# B167X.net
KiCad netlist of a schematic drawn in EAGLE
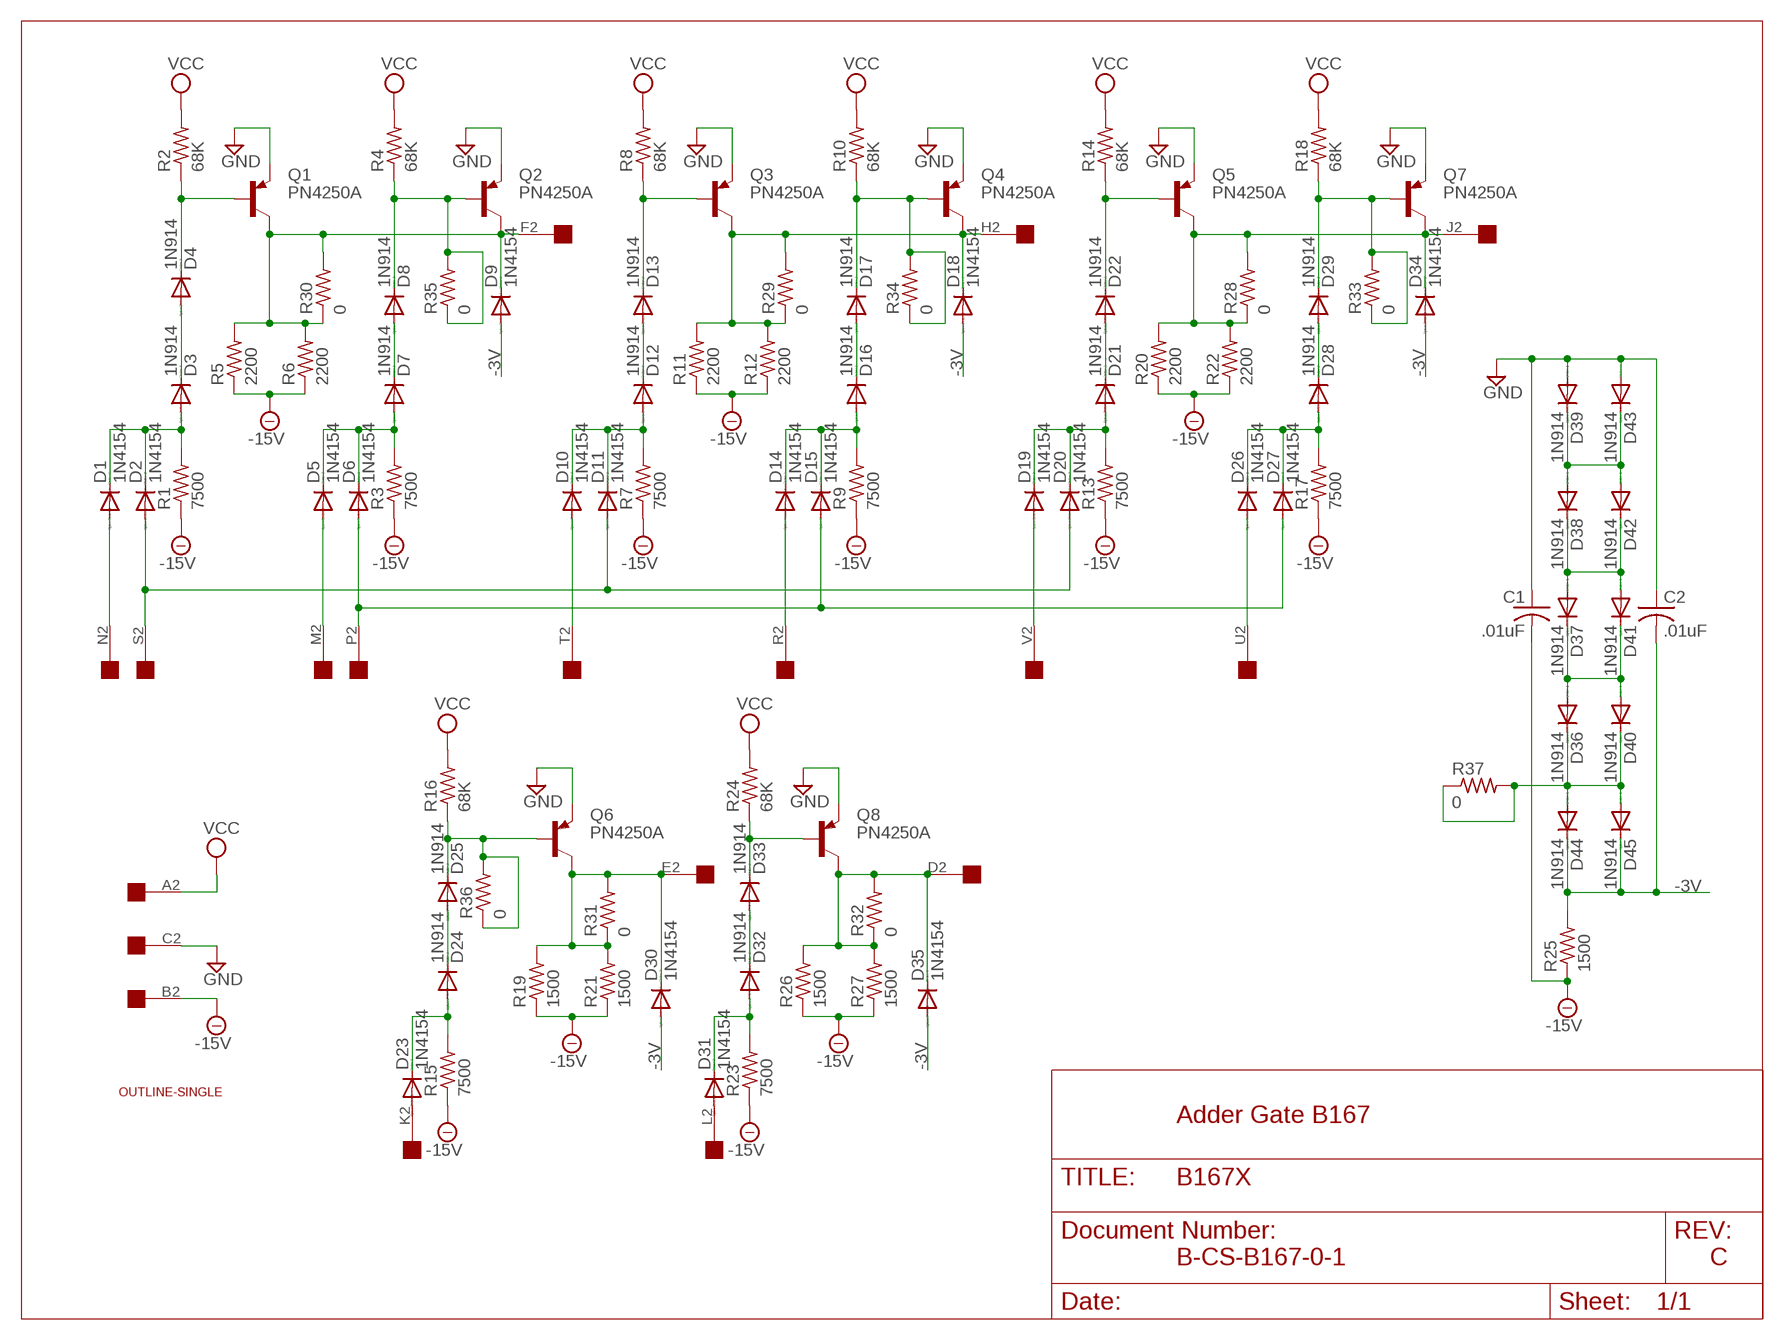
[diagram p0: schematic, sheet 1]

(export (version "E")
  (design (tool "Eeschema 10.0.6"))
  (components
    (comp (ref "C1")
      (value ".01uF")
      (footprint "eagle-import:C063-025X075")
      (libsource (lib "eagle-import") (part "C-US"))
    )
    (comp (ref "C2")
      (value ".01uF")
      (footprint "eagle-import:C063-025X075")
      (libsource (lib "eagle-import") (part "C-US"))
    )
    (comp (ref "D1")
      (value "1N4154")
      (footprint "eagle-import:DO35-10")
      (libsource (lib "eagle-import") (part "DIODE-DO35-10"))
    )
    (comp (ref "D2")
      (value "1N4154")
      (footprint "eagle-import:DO35-10")
      (libsource (lib "eagle-import") (part "DIODE-DO35-10"))
    )
    (comp (ref "D3")
      (value "1N914")
      (footprint "eagle-import:DO35-10")
      (libsource (lib "eagle-import") (part "DIODE-DO35-10"))
    )
    (comp (ref "D4")
      (value "1N914")
      (footprint "eagle-import:DO35-10")
      (libsource (lib "eagle-import") (part "DIODE-DO35-10"))
    )
    (comp (ref "D5")
      (value "1N4154")
      (footprint "eagle-import:DO35-10")
      (libsource (lib "eagle-import") (part "DIODE-DO35-10"))
    )
    (comp (ref "D6")
      (value "1N4154")
      (footprint "eagle-import:DO35-10")
      (libsource (lib "eagle-import") (part "DIODE-DO35-10"))
    )
    (comp (ref "D7")
      (value "1N914")
      (footprint "eagle-import:DO35-10")
      (libsource (lib "eagle-import") (part "DIODE-DO35-10"))
    )
    (comp (ref "D8")
      (value "1N914")
      (footprint "eagle-import:DO35-10")
      (libsource (lib "eagle-import") (part "DIODE-DO35-10"))
    )
    (comp (ref "D9")
      (value "1N4154")
      (footprint "eagle-import:DO35-10")
      (libsource (lib "eagle-import") (part "DIODE-DO35-10"))
    )
    (comp (ref "D10")
      (value "1N4154")
      (footprint "eagle-import:DO35-10")
      (libsource (lib "eagle-import") (part "DIODE-DO35-10"))
    )
    (comp (ref "D11")
      (value "1N4154")
      (footprint "eagle-import:DO35-10")
      (libsource (lib "eagle-import") (part "DIODE-DO35-10"))
    )
    (comp (ref "D12")
      (value "1N914")
      (footprint "eagle-import:DO35-10")
      (libsource (lib "eagle-import") (part "DIODE-DO35-10"))
    )
    (comp (ref "D13")
      (value "1N914")
      (footprint "eagle-import:DO35-10")
      (libsource (lib "eagle-import") (part "DIODE-DO35-10"))
    )
    (comp (ref "D14")
      (value "1N4154")
      (footprint "eagle-import:DO35-10")
      (libsource (lib "eagle-import") (part "DIODE-DO35-10"))
    )
    (comp (ref "D15")
      (value "1N4154")
      (footprint "eagle-import:DO35-10")
      (libsource (lib "eagle-import") (part "DIODE-DO35-10"))
    )
    (comp (ref "D16")
      (value "1N914")
      (footprint "eagle-import:DO35-10")
      (libsource (lib "eagle-import") (part "DIODE-DO35-10"))
    )
    (comp (ref "D17")
      (value "1N914")
      (footprint "eagle-import:DO35-10")
      (libsource (lib "eagle-import") (part "DIODE-DO35-10"))
    )
    (comp (ref "D18")
      (value "1N4154")
      (footprint "eagle-import:DO35-10")
      (libsource (lib "eagle-import") (part "DIODE-DO35-10"))
    )
    (comp (ref "D19")
      (value "1N4154")
      (footprint "eagle-import:DO35-10")
      (libsource (lib "eagle-import") (part "DIODE-DO35-10"))
    )
    (comp (ref "D20")
      (value "1N4154")
      (footprint "eagle-import:DO35-10")
      (libsource (lib "eagle-import") (part "DIODE-DO35-10"))
    )
    (comp (ref "D21")
      (value "1N914")
      (footprint "eagle-import:DO35-10")
      (libsource (lib "eagle-import") (part "DIODE-DO35-10"))
    )
    (comp (ref "D22")
      (value "1N914")
      (footprint "eagle-import:DO35-10")
      (libsource (lib "eagle-import") (part "DIODE-DO35-10"))
    )
    (comp (ref "D23")
      (value "1N4154")
      (footprint "eagle-import:DO35-10")
      (libsource (lib "eagle-import") (part "DIODE-DO35-10"))
    )
    (comp (ref "D24")
      (value "1N914")
      (footprint "eagle-import:DO35-10")
      (libsource (lib "eagle-import") (part "DIODE-DO35-10"))
    )
    (comp (ref "D25")
      (value "1N914")
      (footprint "eagle-import:DO35-10")
      (libsource (lib "eagle-import") (part "DIODE-DO35-10"))
    )
    (comp (ref "D26")
      (value "1N4154")
      (footprint "eagle-import:DO35-10")
      (libsource (lib "eagle-import") (part "DIODE-DO35-10"))
    )
    (comp (ref "D27")
      (value "1N4154")
      (footprint "eagle-import:DO35-10")
      (libsource (lib "eagle-import") (part "DIODE-DO35-10"))
    )
    (comp (ref "D28")
      (value "1N914")
      (footprint "eagle-import:DO35-10")
      (libsource (lib "eagle-import") (part "DIODE-DO35-10"))
    )
    (comp (ref "D29")
      (value "1N914")
      (footprint "eagle-import:DO35-10")
      (libsource (lib "eagle-import") (part "DIODE-DO35-10"))
    )
    (comp (ref "D30")
      (value "1N4154")
      (footprint "eagle-import:DO35-10")
      (libsource (lib "eagle-import") (part "DIODE-DO35-10"))
    )
    (comp (ref "D31")
      (value "1N4154")
      (footprint "eagle-import:DO35-10")
      (libsource (lib "eagle-import") (part "DIODE-DO35-10"))
    )
    (comp (ref "D32")
      (value "1N914")
      (footprint "eagle-import:DO35-10")
      (libsource (lib "eagle-import") (part "DIODE-DO35-10"))
    )
    (comp (ref "D33")
      (value "1N914")
      (footprint "eagle-import:DO35-10")
      (libsource (lib "eagle-import") (part "DIODE-DO35-10"))
    )
    (comp (ref "D34")
      (value "1N4154")
      (footprint "eagle-import:DO35-10")
      (libsource (lib "eagle-import") (part "DIODE-DO35-10"))
    )
    (comp (ref "D35")
      (value "1N4154")
      (footprint "eagle-import:DO35-10")
      (libsource (lib "eagle-import") (part "DIODE-DO35-10"))
    )
    (comp (ref "D36")
      (value "1N914")
      (footprint "eagle-import:DO35-10")
      (libsource (lib "eagle-import") (part "DIODE-DO35-10"))
    )
    (comp (ref "D37")
      (value "1N914")
      (footprint "eagle-import:DO35-10")
      (libsource (lib "eagle-import") (part "DIODE-DO35-10"))
    )
    (comp (ref "D38")
      (value "1N914")
      (footprint "eagle-import:DO35-10")
      (libsource (lib "eagle-import") (part "DIODE-DO35-10"))
    )
    (comp (ref "D39")
      (value "1N914")
      (footprint "eagle-import:DO35-10")
      (libsource (lib "eagle-import") (part "DIODE-DO35-10"))
    )
    (comp (ref "D40")
      (value "1N914")
      (footprint "eagle-import:DO35-10")
      (libsource (lib "eagle-import") (part "DIODE-DO35-10"))
    )
    (comp (ref "D41")
      (value "1N914")
      (footprint "eagle-import:DO35-10")
      (libsource (lib "eagle-import") (part "DIODE-DO35-10"))
    )
    (comp (ref "D42")
      (value "1N914")
      (footprint "eagle-import:DO35-10")
      (libsource (lib "eagle-import") (part "DIODE-DO35-10"))
    )
    (comp (ref "D43")
      (value "1N914")
      (footprint "eagle-import:DO35-10")
      (libsource (lib "eagle-import") (part "DIODE-DO35-10"))
    )
    (comp (ref "D44")
      (value "1N914")
      (footprint "eagle-import:DO35-10")
      (libsource (lib "eagle-import") (part "DIODE-DO35-10"))
    )
    (comp (ref "D45")
      (value "1N914")
      (footprint "eagle-import:DO35-10")
      (libsource (lib "eagle-import") (part "DIODE-DO35-10"))
    )
    (comp (ref "Q1")
      (value "PN4250A")
      (footprint "eagle-import:TO5")
      (libsource (lib "eagle-import") (part "-PNP-TO5"))
    )
    (comp (ref "Q2")
      (value "PN4250A")
      (footprint "eagle-import:TO5")
      (libsource (lib "eagle-import") (part "-PNP-TO5"))
    )
    (comp (ref "Q3")
      (value "PN4250A")
      (footprint "eagle-import:TO5")
      (libsource (lib "eagle-import") (part "-PNP-TO5"))
    )
    (comp (ref "Q4")
      (value "PN4250A")
      (footprint "eagle-import:TO5")
      (libsource (lib "eagle-import") (part "-PNP-TO5"))
    )
    (comp (ref "Q5")
      (value "PN4250A")
      (footprint "eagle-import:TO5")
      (libsource (lib "eagle-import") (part "-PNP-TO5"))
    )
    (comp (ref "Q6")
      (value "PN4250A")
      (footprint "eagle-import:TO5")
      (libsource (lib "eagle-import") (part "-PNP-TO5"))
    )
    (comp (ref "Q7")
      (value "PN4250A")
      (footprint "eagle-import:TO5")
      (libsource (lib "eagle-import") (part "-PNP-TO5"))
    )
    (comp (ref "Q8")
      (value "PN4250A")
      (footprint "eagle-import:TO5")
      (libsource (lib "eagle-import") (part "-PNP-TO5"))
    )
    (comp (ref "R1")
      (value "7500")
      (footprint "eagle-import:0207_10")
      (libsource (lib "eagle-import") (part "R-US_0207/10"))
    )
    (comp (ref "R2")
      (value "68K")
      (footprint "eagle-import:0207_10")
      (libsource (lib "eagle-import") (part "R-US_0207/10"))
    )
    (comp (ref "R3")
      (value "7500")
      (footprint "eagle-import:0207_10")
      (libsource (lib "eagle-import") (part "R-US_0207/10"))
    )
    (comp (ref "R4")
      (value "68K")
      (footprint "eagle-import:0207_10")
      (libsource (lib "eagle-import") (part "R-US_0207/10"))
    )
    (comp (ref "R5")
      (value "2200")
      (footprint "eagle-import:0207_10")
      (libsource (lib "eagle-import") (part "R-US_0207/10"))
    )
    (comp (ref "R6")
      (value "2200")
      (footprint "eagle-import:0207_10")
      (libsource (lib "eagle-import") (part "R-US_0207/10"))
    )
    (comp (ref "R7")
      (value "7500")
      (footprint "eagle-import:0207_10")
      (libsource (lib "eagle-import") (part "R-US_0207/10"))
    )
    (comp (ref "R8")
      (value "68K")
      (footprint "eagle-import:0207_10")
      (libsource (lib "eagle-import") (part "R-US_0207/10"))
    )
    (comp (ref "R9")
      (value "7500")
      (footprint "eagle-import:0207_10")
      (libsource (lib "eagle-import") (part "R-US_0207/10"))
    )
    (comp (ref "R10")
      (value "68K")
      (footprint "eagle-import:0207_10")
      (libsource (lib "eagle-import") (part "R-US_0207/10"))
    )
    (comp (ref "R11")
      (value "2200")
      (footprint "eagle-import:0207_10")
      (libsource (lib "eagle-import") (part "R-US_0207/10"))
    )
    (comp (ref "R12")
      (value "2200")
      (footprint "eagle-import:0207_10")
      (libsource (lib "eagle-import") (part "R-US_0207/10"))
    )
    (comp (ref "R13")
      (value "7500")
      (footprint "eagle-import:0207_10")
      (libsource (lib "eagle-import") (part "R-US_0207/10"))
    )
    (comp (ref "R14")
      (value "68K")
      (footprint "eagle-import:0207_10")
      (libsource (lib "eagle-import") (part "R-US_0207/10"))
    )
    (comp (ref "R15")
      (value "7500")
      (footprint "eagle-import:0207_10")
      (libsource (lib "eagle-import") (part "R-US_0207/10"))
    )
    (comp (ref "R16")
      (value "68K")
      (footprint "eagle-import:0207_10")
      (libsource (lib "eagle-import") (part "R-US_0207/10"))
    )
    (comp (ref "R17")
      (value "7500")
      (footprint "eagle-import:0207_10")
      (libsource (lib "eagle-import") (part "R-US_0207/10"))
    )
    (comp (ref "R18")
      (value "68K")
      (footprint "eagle-import:0207_10")
      (libsource (lib "eagle-import") (part "R-US_0207/10"))
    )
    (comp (ref "R19")
      (value "1500")
      (footprint "eagle-import:0207_10")
      (libsource (lib "eagle-import") (part "R-US_0207/10"))
    )
    (comp (ref "R20")
      (value "2200")
      (footprint "eagle-import:0207_10")
      (libsource (lib "eagle-import") (part "R-US_0207/10"))
    )
    (comp (ref "R21")
      (value "1500")
      (footprint "eagle-import:0207_10")
      (libsource (lib "eagle-import") (part "R-US_0207/10"))
    )
    (comp (ref "R22")
      (value "2200")
      (footprint "eagle-import:0207_10")
      (libsource (lib "eagle-import") (part "R-US_0207/10"))
    )
    (comp (ref "R23")
      (value "7500")
      (footprint "eagle-import:0207_10")
      (libsource (lib "eagle-import") (part "R-US_0207/10"))
    )
    (comp (ref "R24")
      (value "68K")
      (footprint "eagle-import:0207_10")
      (libsource (lib "eagle-import") (part "R-US_0207/10"))
    )
    (comp (ref "R25")
      (value "1500")
      (footprint "eagle-import:0207_10")
      (libsource (lib "eagle-import") (part "R-US_0207/10"))
    )
    (comp (ref "R26")
      (value "1500")
      (footprint "eagle-import:0207_10")
      (libsource (lib "eagle-import") (part "R-US_0207/10"))
    )
    (comp (ref "R27")
      (value "1500")
      (footprint "eagle-import:0207_10")
      (libsource (lib "eagle-import") (part "R-US_0207/10"))
    )
    (comp (ref "R28")
      (value "0")
      (footprint "eagle-import:0207_10")
      (libsource (lib "eagle-import") (part "R-US_0207/10"))
    )
    (comp (ref "R29")
      (value "0")
      (footprint "eagle-import:0207_10")
      (libsource (lib "eagle-import") (part "R-US_0207/10"))
    )
    (comp (ref "R30")
      (value "0")
      (footprint "eagle-import:0207_10")
      (libsource (lib "eagle-import") (part "R-US_0207/10"))
    )
    (comp (ref "R31")
      (value "0")
      (footprint "eagle-import:0207_10")
      (libsource (lib "eagle-import") (part "R-US_0207/10"))
    )
    (comp (ref "R32")
      (value "0")
      (footprint "eagle-import:0207_10")
      (libsource (lib "eagle-import") (part "R-US_0207/10"))
    )
    (comp (ref "R33")
      (value "0")
      (footprint "eagle-import:0207_10")
      (libsource (lib "eagle-import") (part "R-US_0207/10"))
    )
    (comp (ref "R34")
      (value "0")
      (footprint "eagle-import:0207_10")
      (libsource (lib "eagle-import") (part "R-US_0207/10"))
    )
    (comp (ref "R35")
      (value "0")
      (footprint "eagle-import:0207_10")
      (libsource (lib "eagle-import") (part "R-US_0207/10"))
    )
    (comp (ref "R36")
      (value "0")
      (footprint "eagle-import:0207_10")
      (libsource (lib "eagle-import") (part "R-US_0207/10"))
    )
    (comp (ref "R37")
      (value "0")
      (footprint "eagle-import:0207_10")
      (libsource (lib "eagle-import") (part "R-US_0207/10"))
    )
    (comp (ref "U$1")
      (value "OUTLINE-SINGLE")
      (footprint "eagle-import:SINGLE")
      (libsource (lib "eagle-import") (part "OUTLINE-SINGLE"))
    )
    (comp (ref "U$2")
      (value "EDGE-1")
      (footprint "eagle-import:EDGE-CON1")
      (libsource (lib "eagle-import") (part "EDGE-1"))
    )
  )
  (nets
    (net (code "1") (name "-15V") (class "Default")
      (node (ref "C1") (pin "2") (pinfunction "2_2") (pintype "passive"))
      (node (ref "R1") (pin "1") (pinfunction "1_1") (pintype "passive"))
      (node (ref "R11") (pin "1") (pinfunction "1_1") (pintype "passive"))
      (node (ref "R12") (pin "1") (pinfunction "1_1") (pintype "passive"))
      (node (ref "R13") (pin "1") (pinfunction "1_1") (pintype "passive"))
      (node (ref "R15") (pin "1") (pinfunction "1_1") (pintype "passive"))
      (node (ref "R17") (pin "1") (pinfunction "1_1") (pintype "passive"))
      (node (ref "R19") (pin "1") (pinfunction "1_1") (pintype "passive"))
      (node (ref "R20") (pin "1") (pinfunction "1_1") (pintype "passive"))
      (node (ref "R21") (pin "1") (pinfunction "1_1") (pintype "passive"))
      (node (ref "R22") (pin "1") (pinfunction "1_1") (pintype "passive"))
      (node (ref "R23") (pin "1") (pinfunction "1_1") (pintype "passive"))
      (node (ref "R25") (pin "1") (pinfunction "1_1") (pintype "passive"))
      (node (ref "R26") (pin "1") (pinfunction "1_1") (pintype "passive"))
      (node (ref "R27") (pin "1") (pinfunction "1_1") (pintype "passive"))
      (node (ref "R3") (pin "1") (pinfunction "1_1") (pintype "passive"))
      (node (ref "R5") (pin "1") (pinfunction "1_1") (pintype "passive"))
      (node (ref "R6") (pin "1") (pinfunction "1_1") (pintype "passive"))
      (node (ref "R7") (pin "1") (pinfunction "1_1") (pintype "passive"))
      (node (ref "R9") (pin "1") (pinfunction "1_1") (pintype "passive"))
      (node (ref "U$2") (pin "B2") (pinfunction "1_B2") (pintype "bidirectional"))
    )
    (net (code "2") (name "/-3V") (class "Default")
      (node (ref "C2") (pin "2") (pinfunction "2_2") (pintype "passive"))
      (node (ref "D18") (pin "A") (pinfunction "A_A") (pintype "passive"))
      (node (ref "D30") (pin "A") (pinfunction "A_A") (pintype "passive"))
      (node (ref "D34") (pin "A") (pinfunction "A_A") (pintype "passive"))
      (node (ref "D35") (pin "A") (pinfunction "A_A") (pintype "passive"))
      (node (ref "D44") (pin "C") (pinfunction "C_C") (pintype "passive"))
      (node (ref "D45") (pin "C") (pinfunction "C_C") (pintype "passive"))
      (node (ref "D9") (pin "A") (pinfunction "A_A") (pintype "passive"))
      (node (ref "R25") (pin "2") (pinfunction "2_2") (pintype "passive"))
    )
    (net (code "3") (name "GND") (class "Default")
      (node (ref "C1") (pin "1") (pinfunction "1_1") (pintype "passive"))
      (node (ref "C2") (pin "1") (pinfunction "1_1") (pintype "passive"))
      (node (ref "D39") (pin "A") (pinfunction "A_A") (pintype "passive"))
      (node (ref "D43") (pin "A") (pinfunction "A_A") (pintype "passive"))
      (node (ref "Q1") (pin "1") (pinfunction "E_1") (pintype "passive"))
      (node (ref "Q2") (pin "1") (pinfunction "E_1") (pintype "passive"))
      (node (ref "Q3") (pin "1") (pinfunction "E_1") (pintype "passive"))
      (node (ref "Q4") (pin "1") (pinfunction "E_1") (pintype "passive"))
      (node (ref "Q5") (pin "1") (pinfunction "E_1") (pintype "passive"))
      (node (ref "Q6") (pin "1") (pinfunction "E_1") (pintype "passive"))
      (node (ref "Q7") (pin "1") (pinfunction "E_1") (pintype "passive"))
      (node (ref "Q8") (pin "1") (pinfunction "E_1") (pintype "passive"))
      (node (ref "U$2") (pin "C2") (pinfunction "1_C2") (pintype "bidirectional"))
    )
    (net (code "4") (name "Net-(D1-PadC)") (class "Default")
      (node (ref "D1") (pin "C") (pinfunction "C_C") (pintype "passive"))
      (node (ref "D2") (pin "C") (pinfunction "C_C") (pintype "passive"))
      (node (ref "D3") (pin "A") (pinfunction "A_A") (pintype "passive"))
      (node (ref "R1") (pin "2") (pinfunction "2_2") (pintype "passive"))
    )
    (net (code "5") (name "Net-(D3-PadC)") (class "Default")
      (node (ref "D3") (pin "C") (pinfunction "C_C") (pintype "passive"))
      (node (ref "D4") (pin "A") (pinfunction "A_A") (pintype "passive"))
    )
    (net (code "6") (name "Net-(D5-PadC)") (class "Default")
      (node (ref "D5") (pin "C") (pinfunction "C_C") (pintype "passive"))
      (node (ref "D6") (pin "C") (pinfunction "C_C") (pintype "passive"))
      (node (ref "D7") (pin "A") (pinfunction "A_A") (pintype "passive"))
      (node (ref "R3") (pin "2") (pinfunction "2_2") (pintype "passive"))
    )
    (net (code "7") (name "Net-(D7-PadC)") (class "Default")
      (node (ref "D7") (pin "C") (pinfunction "C_C") (pintype "passive"))
      (node (ref "D8") (pin "A") (pinfunction "A_A") (pintype "passive"))
    )
    (net (code "8") (name "Net-(D10-PadC)") (class "Default")
      (node (ref "D10") (pin "C") (pinfunction "C_C") (pintype "passive"))
      (node (ref "D11") (pin "C") (pinfunction "C_C") (pintype "passive"))
      (node (ref "D12") (pin "A") (pinfunction "A_A") (pintype "passive"))
      (node (ref "R7") (pin "2") (pinfunction "2_2") (pintype "passive"))
    )
    (net (code "9") (name "Net-(D12-PadC)") (class "Default")
      (node (ref "D12") (pin "C") (pinfunction "C_C") (pintype "passive"))
      (node (ref "D13") (pin "A") (pinfunction "A_A") (pintype "passive"))
    )
    (net (code "10") (name "Net-(D14-PadC)") (class "Default")
      (node (ref "D14") (pin "C") (pinfunction "C_C") (pintype "passive"))
      (node (ref "D15") (pin "C") (pinfunction "C_C") (pintype "passive"))
      (node (ref "D16") (pin "A") (pinfunction "A_A") (pintype "passive"))
      (node (ref "R9") (pin "2") (pinfunction "2_2") (pintype "passive"))
    )
    (net (code "11") (name "Net-(D16-PadC)") (class "Default")
      (node (ref "D16") (pin "C") (pinfunction "C_C") (pintype "passive"))
      (node (ref "D17") (pin "A") (pinfunction "A_A") (pintype "passive"))
    )
    (net (code "12") (name "Net-(D19-PadC)") (class "Default")
      (node (ref "D19") (pin "C") (pinfunction "C_C") (pintype "passive"))
      (node (ref "D20") (pin "C") (pinfunction "C_C") (pintype "passive"))
      (node (ref "D21") (pin "A") (pinfunction "A_A") (pintype "passive"))
      (node (ref "R13") (pin "2") (pinfunction "2_2") (pintype "passive"))
    )
    (net (code "13") (name "Net-(D21-PadC)") (class "Default")
      (node (ref "D21") (pin "C") (pinfunction "C_C") (pintype "passive"))
      (node (ref "D22") (pin "A") (pinfunction "A_A") (pintype "passive"))
    )
    (net (code "14") (name "Net-(D23-PadC)") (class "Default")
      (node (ref "D23") (pin "C") (pinfunction "C_C") (pintype "passive"))
      (node (ref "D24") (pin "A") (pinfunction "A_A") (pintype "passive"))
      (node (ref "R15") (pin "2") (pinfunction "2_2") (pintype "passive"))
    )
    (net (code "15") (name "Net-(D24-PadC)") (class "Default")
      (node (ref "D24") (pin "C") (pinfunction "C_C") (pintype "passive"))
      (node (ref "D25") (pin "A") (pinfunction "A_A") (pintype "passive"))
    )
    (net (code "16") (name "Net-(D26-PadC)") (class "Default")
      (node (ref "D26") (pin "C") (pinfunction "C_C") (pintype "passive"))
      (node (ref "D27") (pin "C") (pinfunction "C_C") (pintype "passive"))
      (node (ref "D28") (pin "A") (pinfunction "A_A") (pintype "passive"))
      (node (ref "R17") (pin "2") (pinfunction "2_2") (pintype "passive"))
    )
    (net (code "17") (name "Net-(D28-PadC)") (class "Default")
      (node (ref "D28") (pin "C") (pinfunction "C_C") (pintype "passive"))
      (node (ref "D29") (pin "A") (pinfunction "A_A") (pintype "passive"))
    )
    (net (code "18") (name "Net-(D31-PadC)") (class "Default")
      (node (ref "D31") (pin "C") (pinfunction "C_C") (pintype "passive"))
      (node (ref "D32") (pin "A") (pinfunction "A_A") (pintype "passive"))
      (node (ref "R23") (pin "2") (pinfunction "2_2") (pintype "passive"))
    )
    (net (code "19") (name "Net-(D32-PadC)") (class "Default")
      (node (ref "D32") (pin "C") (pinfunction "C_C") (pintype "passive"))
      (node (ref "D33") (pin "A") (pinfunction "A_A") (pintype "passive"))
    )
    (net (code "20") (name "Net-(D36-PadA)") (class "Default")
      (node (ref "D36") (pin "A") (pinfunction "A_A") (pintype "passive"))
      (node (ref "D37") (pin "C") (pinfunction "C_C") (pintype "passive"))
      (node (ref "D40") (pin "A") (pinfunction "A_A") (pintype "passive"))
      (node (ref "D41") (pin "C") (pinfunction "C_C") (pintype "passive"))
    )
    (net (code "21") (name "Net-(D36-PadC)") (class "Default")
      (node (ref "D36") (pin "C") (pinfunction "C_C") (pintype "passive"))
      (node (ref "D40") (pin "C") (pinfunction "C_C") (pintype "passive"))
      (node (ref "D44") (pin "A") (pinfunction "A_A") (pintype "passive"))
      (node (ref "D45") (pin "A") (pinfunction "A_A") (pintype "passive"))
      (node (ref "R37") (pin "1") (pinfunction "1_1") (pintype "passive"))
      (node (ref "R37") (pin "2") (pinfunction "2_2") (pintype "passive"))
    )
    (net (code "22") (name "Net-(D37-PadA)") (class "Default")
      (node (ref "D37") (pin "A") (pinfunction "A_A") (pintype "passive"))
      (node (ref "D38") (pin "C") (pinfunction "C_C") (pintype "passive"))
      (node (ref "D41") (pin "A") (pinfunction "A_A") (pintype "passive"))
      (node (ref "D42") (pin "C") (pinfunction "C_C") (pintype "passive"))
    )
    (net (code "23") (name "Net-(D38-PadA)") (class "Default")
      (node (ref "D38") (pin "A") (pinfunction "A_A") (pintype "passive"))
      (node (ref "D39") (pin "C") (pinfunction "C_C") (pintype "passive"))
      (node (ref "D42") (pin "A") (pinfunction "A_A") (pintype "passive"))
      (node (ref "D43") (pin "C") (pinfunction "C_C") (pintype "passive"))
    )
    (net (code "24") (name "Net-(Q1-B)") (class "Default")
      (node (ref "D4") (pin "C") (pinfunction "C_C") (pintype "passive"))
      (node (ref "Q1") (pin "2") (pinfunction "B_2") (pintype "passive"))
      (node (ref "R2") (pin "1") (pinfunction "1_1") (pintype "passive"))
    )
    (net (code "25") (name "Net-(Q1-C)") (class "Default")
      (node (ref "D9") (pin "C") (pinfunction "C_C") (pintype "passive"))
      (node (ref "Q1") (pin "3") (pinfunction "C_3") (pintype "passive"))
      (node (ref "Q2") (pin "3") (pinfunction "C_3") (pintype "passive"))
      (node (ref "R30") (pin "1") (pinfunction "1_1") (pintype "passive"))
      (node (ref "R30") (pin "2") (pinfunction "2_2") (pintype "passive"))
      (node (ref "R5") (pin "2") (pinfunction "2_2") (pintype "passive"))
      (node (ref "R6") (pin "2") (pinfunction "2_2") (pintype "passive"))
      (node (ref "U$2") (pin "F2") (pinfunction "1_F2") (pintype "bidirectional"))
    )
    (net (code "26") (name "Net-(Q2-B)") (class "Default")
      (node (ref "D8") (pin "C") (pinfunction "C_C") (pintype "passive"))
      (node (ref "Q2") (pin "2") (pinfunction "B_2") (pintype "passive"))
      (node (ref "R35") (pin "1") (pinfunction "1_1") (pintype "passive"))
      (node (ref "R35") (pin "2") (pinfunction "2_2") (pintype "passive"))
      (node (ref "R4") (pin "1") (pinfunction "1_1") (pintype "passive"))
    )
    (net (code "27") (name "Net-(Q3-B)") (class "Default")
      (node (ref "D13") (pin "C") (pinfunction "C_C") (pintype "passive"))
      (node (ref "Q3") (pin "2") (pinfunction "B_2") (pintype "passive"))
      (node (ref "R8") (pin "1") (pinfunction "1_1") (pintype "passive"))
    )
    (net (code "28") (name "Net-(Q3-C)") (class "Default")
      (node (ref "D18") (pin "C") (pinfunction "C_C") (pintype "passive"))
      (node (ref "Q3") (pin "3") (pinfunction "C_3") (pintype "passive"))
      (node (ref "Q4") (pin "3") (pinfunction "C_3") (pintype "passive"))
      (node (ref "R11") (pin "2") (pinfunction "2_2") (pintype "passive"))
      (node (ref "R12") (pin "2") (pinfunction "2_2") (pintype "passive"))
      (node (ref "R29") (pin "1") (pinfunction "1_1") (pintype "passive"))
      (node (ref "R29") (pin "2") (pinfunction "2_2") (pintype "passive"))
      (node (ref "U$2") (pin "H2") (pinfunction "1_H2") (pintype "bidirectional"))
    )
    (net (code "29") (name "Net-(Q4-B)") (class "Default")
      (node (ref "D17") (pin "C") (pinfunction "C_C") (pintype "passive"))
      (node (ref "Q4") (pin "2") (pinfunction "B_2") (pintype "passive"))
      (node (ref "R10") (pin "1") (pinfunction "1_1") (pintype "passive"))
      (node (ref "R34") (pin "1") (pinfunction "1_1") (pintype "passive"))
      (node (ref "R34") (pin "2") (pinfunction "2_2") (pintype "passive"))
    )
    (net (code "30") (name "Net-(Q5-B)") (class "Default")
      (node (ref "D22") (pin "C") (pinfunction "C_C") (pintype "passive"))
      (node (ref "Q5") (pin "2") (pinfunction "B_2") (pintype "passive"))
      (node (ref "R14") (pin "1") (pinfunction "1_1") (pintype "passive"))
    )
    (net (code "31") (name "Net-(Q5-C)") (class "Default")
      (node (ref "D34") (pin "C") (pinfunction "C_C") (pintype "passive"))
      (node (ref "Q5") (pin "3") (pinfunction "C_3") (pintype "passive"))
      (node (ref "Q7") (pin "3") (pinfunction "C_3") (pintype "passive"))
      (node (ref "R20") (pin "2") (pinfunction "2_2") (pintype "passive"))
      (node (ref "R22") (pin "2") (pinfunction "2_2") (pintype "passive"))
      (node (ref "R28") (pin "1") (pinfunction "1_1") (pintype "passive"))
      (node (ref "R28") (pin "2") (pinfunction "2_2") (pintype "passive"))
      (node (ref "U$2") (pin "J2") (pinfunction "1_J2") (pintype "bidirectional"))
    )
    (net (code "32") (name "Net-(Q6-B)") (class "Default")
      (node (ref "D25") (pin "C") (pinfunction "C_C") (pintype "passive"))
      (node (ref "Q6") (pin "2") (pinfunction "B_2") (pintype "passive"))
      (node (ref "R16") (pin "1") (pinfunction "1_1") (pintype "passive"))
      (node (ref "R36") (pin "1") (pinfunction "1_1") (pintype "passive"))
      (node (ref "R36") (pin "2") (pinfunction "2_2") (pintype "passive"))
    )
    (net (code "33") (name "Net-(Q6-C)") (class "Default")
      (node (ref "D30") (pin "C") (pinfunction "C_C") (pintype "passive"))
      (node (ref "Q6") (pin "3") (pinfunction "C_3") (pintype "passive"))
      (node (ref "R19") (pin "2") (pinfunction "2_2") (pintype "passive"))
      (node (ref "R21") (pin "2") (pinfunction "2_2") (pintype "passive"))
      (node (ref "R31") (pin "1") (pinfunction "1_1") (pintype "passive"))
      (node (ref "R31") (pin "2") (pinfunction "2_2") (pintype "passive"))
      (node (ref "U$2") (pin "E2") (pinfunction "1_E2") (pintype "bidirectional"))
    )
    (net (code "34") (name "Net-(Q7-B)") (class "Default")
      (node (ref "D29") (pin "C") (pinfunction "C_C") (pintype "passive"))
      (node (ref "Q7") (pin "2") (pinfunction "B_2") (pintype "passive"))
      (node (ref "R18") (pin "1") (pinfunction "1_1") (pintype "passive"))
      (node (ref "R33") (pin "1") (pinfunction "1_1") (pintype "passive"))
      (node (ref "R33") (pin "2") (pinfunction "2_2") (pintype "passive"))
    )
    (net (code "35") (name "Net-(Q8-B)") (class "Default")
      (node (ref "D33") (pin "C") (pinfunction "C_C") (pintype "passive"))
      (node (ref "Q8") (pin "2") (pinfunction "B_2") (pintype "passive"))
      (node (ref "R24") (pin "1") (pinfunction "1_1") (pintype "passive"))
    )
    (net (code "36") (name "Net-(Q8-C)") (class "Default")
      (node (ref "D35") (pin "C") (pinfunction "C_C") (pintype "passive"))
      (node (ref "Q8") (pin "3") (pinfunction "C_3") (pintype "passive"))
      (node (ref "R26") (pin "2") (pinfunction "2_2") (pintype "passive"))
      (node (ref "R27") (pin "2") (pinfunction "2_2") (pintype "passive"))
      (node (ref "R32") (pin "1") (pinfunction "1_1") (pintype "passive"))
      (node (ref "R32") (pin "2") (pinfunction "2_2") (pintype "passive"))
      (node (ref "U$2") (pin "D2") (pinfunction "1_D2") (pintype "bidirectional"))
    )
    (net (code "37") (name "Net-(U$2I-1)") (class "Default")
      (node (ref "D23") (pin "A") (pinfunction "A_A") (pintype "passive"))
      (node (ref "U$2") (pin "K2") (pinfunction "1_K2") (pintype "bidirectional"))
    )
    (net (code "38") (name "Net-(U$2J-1)") (class "Default")
      (node (ref "D31") (pin "A") (pinfunction "A_A") (pintype "passive"))
      (node (ref "U$2") (pin "L2") (pinfunction "1_L2") (pintype "bidirectional"))
    )
    (net (code "39") (name "Net-(U$2K-1)") (class "Default")
      (node (ref "D5") (pin "A") (pinfunction "A_A") (pintype "passive"))
      (node (ref "U$2") (pin "M2") (pinfunction "1_M2") (pintype "bidirectional"))
    )
    (net (code "40") (name "Net-(U$2L-1)") (class "Default")
      (node (ref "D1") (pin "A") (pinfunction "A_A") (pintype "passive"))
      (node (ref "U$2") (pin "N2") (pinfunction "1_N2") (pintype "bidirectional"))
    )
    (net (code "41") (name "Net-(U$2M-1)") (class "Default")
      (node (ref "D15") (pin "A") (pinfunction "A_A") (pintype "passive"))
      (node (ref "D27") (pin "A") (pinfunction "A_A") (pintype "passive"))
      (node (ref "D6") (pin "A") (pinfunction "A_A") (pintype "passive"))
      (node (ref "U$2") (pin "P2") (pinfunction "1_P2") (pintype "bidirectional"))
    )
    (net (code "42") (name "Net-(U$2N-1)") (class "Default")
      (node (ref "D14") (pin "A") (pinfunction "A_A") (pintype "passive"))
      (node (ref "U$2") (pin "R2") (pinfunction "1_R2") (pintype "bidirectional"))
    )
    (net (code "43") (name "Net-(U$2O-1)") (class "Default")
      (node (ref "D11") (pin "A") (pinfunction "A_A") (pintype "passive"))
      (node (ref "D2") (pin "A") (pinfunction "A_A") (pintype "passive"))
      (node (ref "D20") (pin "A") (pinfunction "A_A") (pintype "passive"))
      (node (ref "U$2") (pin "S2") (pinfunction "1_S2") (pintype "bidirectional"))
    )
    (net (code "44") (name "Net-(U$2P-1)") (class "Default")
      (node (ref "D10") (pin "A") (pinfunction "A_A") (pintype "passive"))
      (node (ref "U$2") (pin "T2") (pinfunction "1_T2") (pintype "bidirectional"))
    )
    (net (code "45") (name "Net-(U$2Q-1)") (class "Default")
      (node (ref "D26") (pin "A") (pinfunction "A_A") (pintype "passive"))
      (node (ref "U$2") (pin "U2") (pinfunction "1_U2") (pintype "bidirectional"))
    )
    (net (code "46") (name "Net-(U$2R-1)") (class "Default")
      (node (ref "D19") (pin "A") (pinfunction "A_A") (pintype "passive"))
      (node (ref "U$2") (pin "V2") (pinfunction "1_V2") (pintype "bidirectional"))
    )
    (net (code "47") (name "VCC") (class "Default")
      (node (ref "R10") (pin "2") (pinfunction "2_2") (pintype "passive"))
      (node (ref "R14") (pin "2") (pinfunction "2_2") (pintype "passive"))
      (node (ref "R16") (pin "2") (pinfunction "2_2") (pintype "passive"))
      (node (ref "R18") (pin "2") (pinfunction "2_2") (pintype "passive"))
      (node (ref "R2") (pin "2") (pinfunction "2_2") (pintype "passive"))
      (node (ref "R24") (pin "2") (pinfunction "2_2") (pintype "passive"))
      (node (ref "R4") (pin "2") (pinfunction "2_2") (pintype "passive"))
      (node (ref "R8") (pin "2") (pinfunction "2_2") (pintype "passive"))
      (node (ref "U$2") (pin "A2") (pinfunction "1_A2") (pintype "bidirectional"))
    )
  )
)
